# 1-Schematic_LoRaRice_node1.net
KiCad netlist of a schematic drawn in EasyEDA
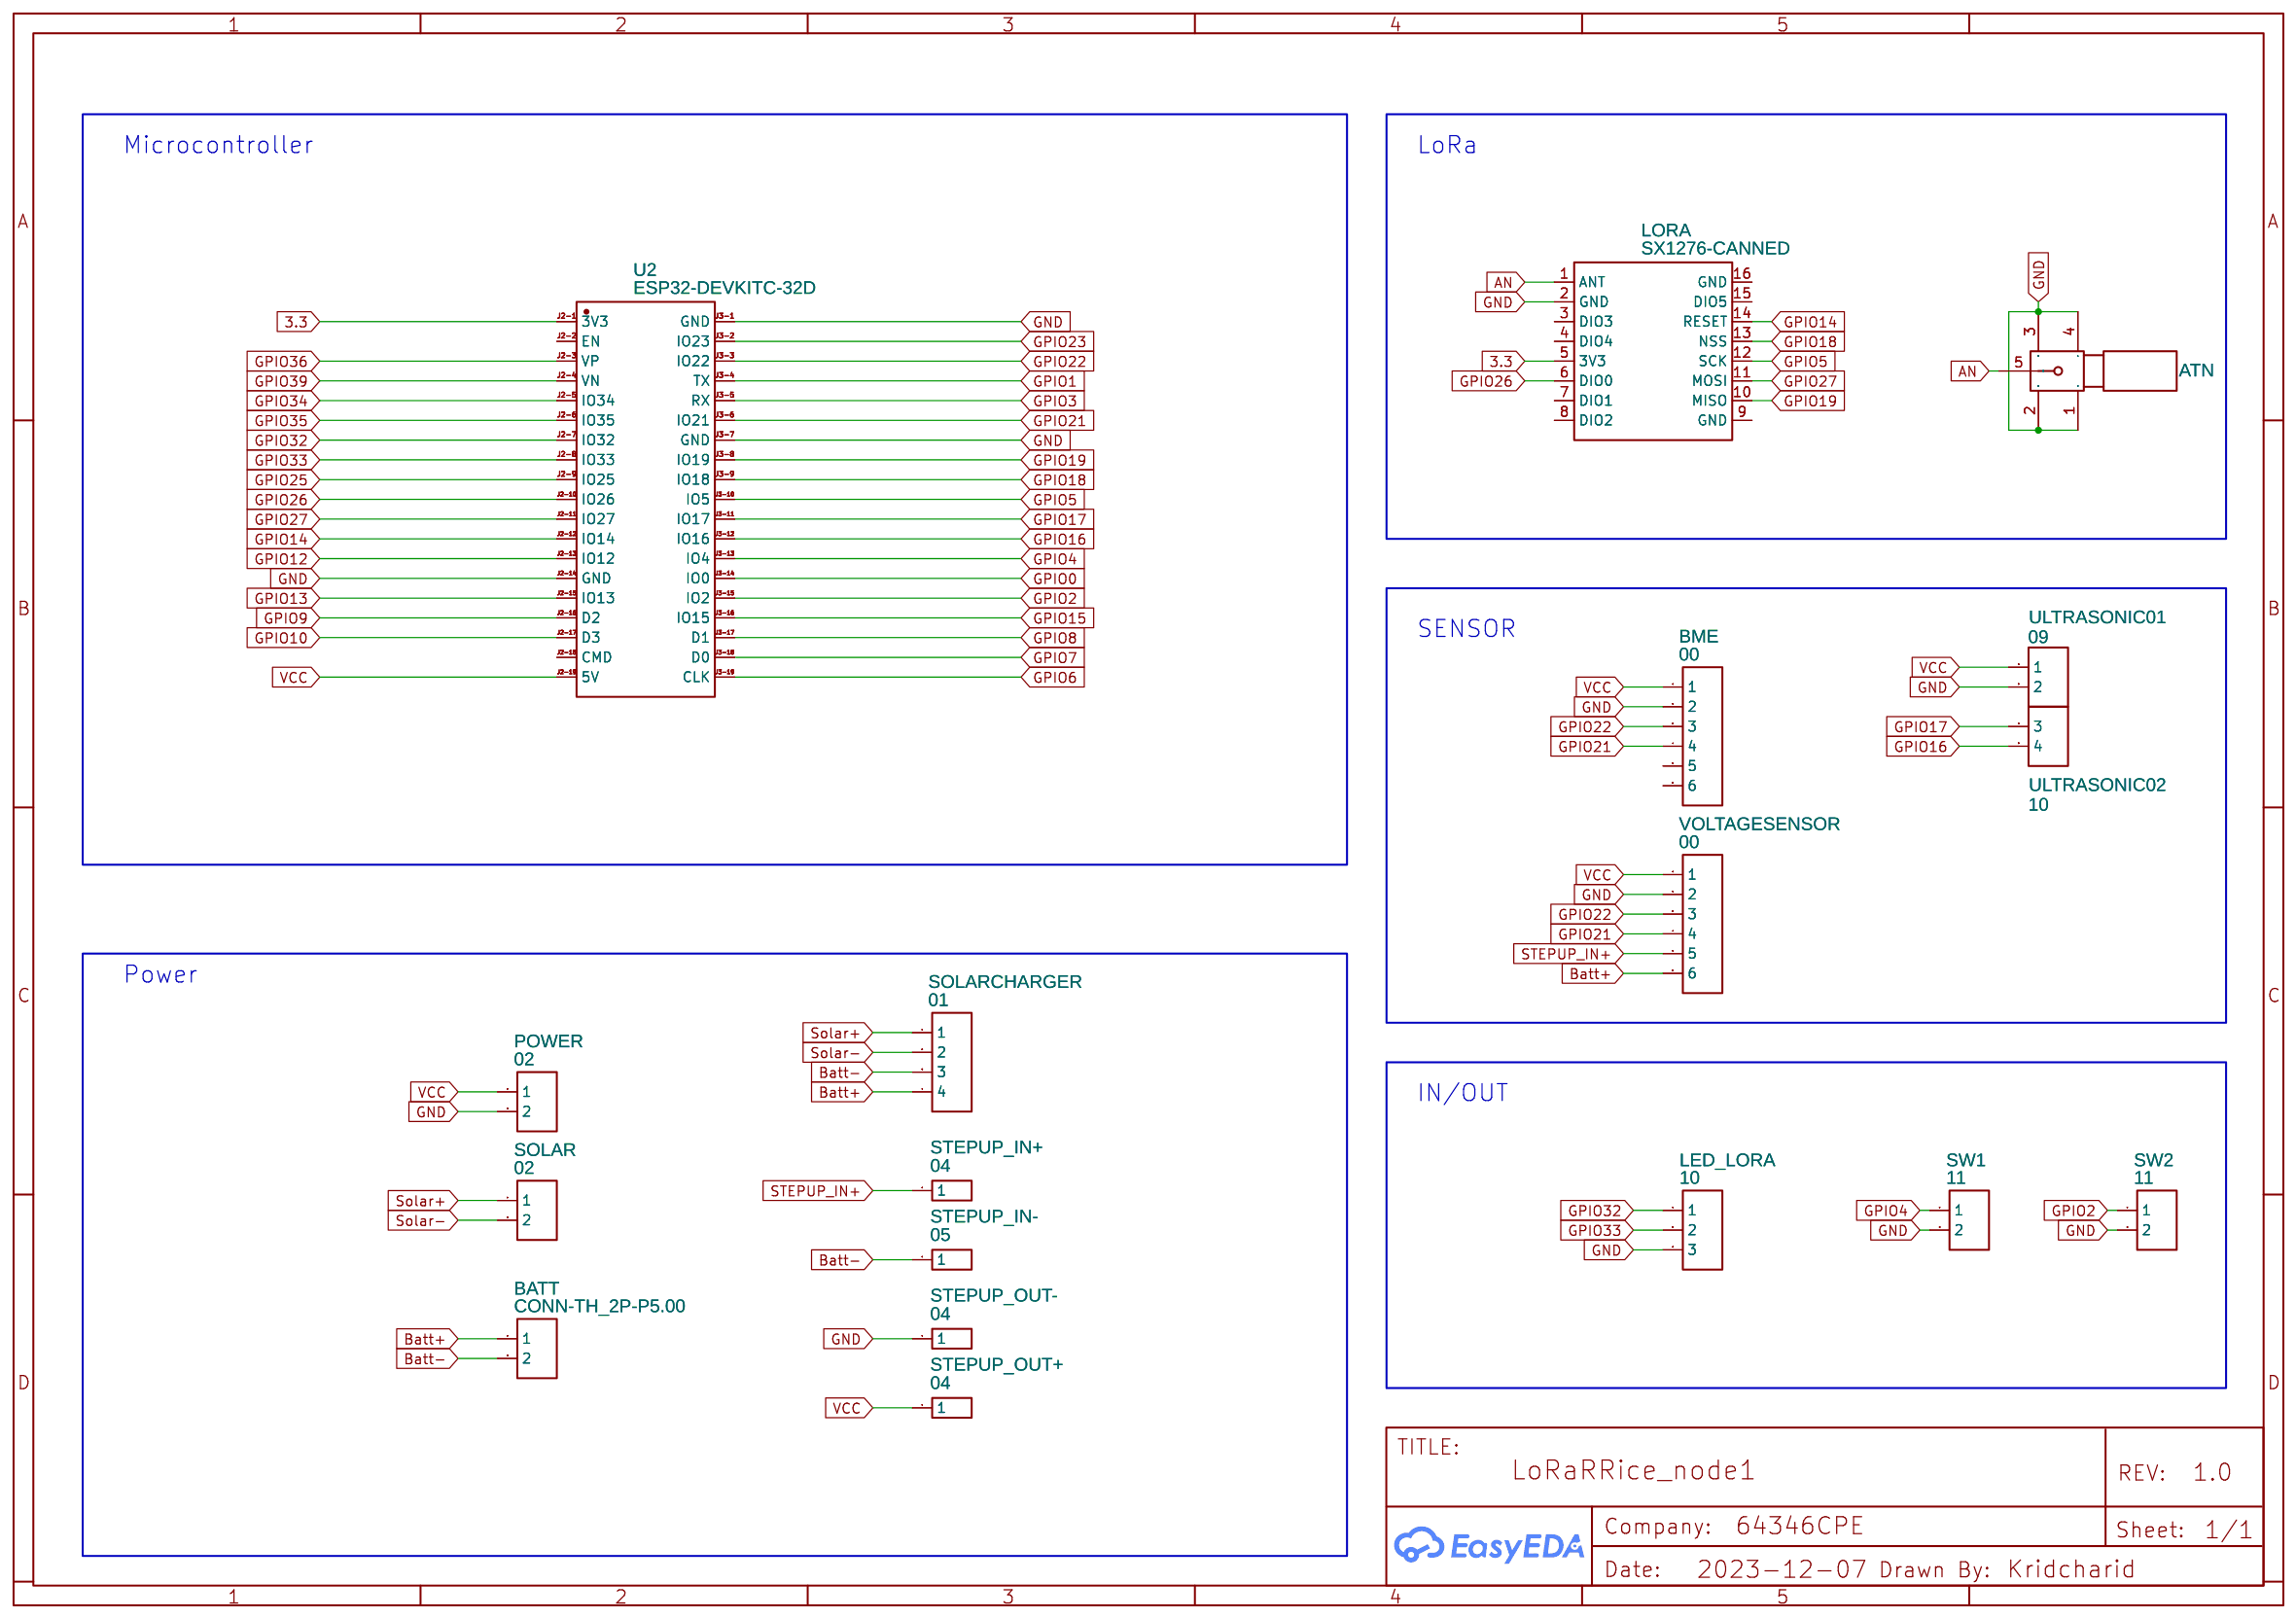
[diagram p0: schematic sheet]

(export (version "E")
  (design (tool "Eeschema 10.0.6"))
  (components
    (comp (ref "BATT") (value "CONN-TH_2P-P5.00") (libsource (lib "") (part "CONN-TH_2P-P5.00_5")))
    (comp (ref "BME") (value "00") (libsource (lib "") (part "HDR-F-2.54_1x6_1")))
    (comp (ref "LED_LORA") (value "10") (libsource (lib "") (part "CONN-TH_3P-P5.00")))
    (comp (ref "LORA")
      (value "SX1276-CANNED")
      (fields (field (name "Manufacturer Part") "LoRa1276-C1") (field (name "Manufacturer") "G-NiceRF"))
      (libsource (lib "") (part "SX1276-CANNED"))
    )
    (comp (ref "POWER") (value "02") (libsource (lib "") (part "CONN-TH_2P-P5.00")))
    (comp (ref "RF1")
      (value "ATN")
      (fields
        (field (name "Manufacturer Part") "BWSMA-KE-P001")
        (field (name "Manufacturer") "BAT WIRELESS(蝙蝠无线)")
      )
      (libsource (lib "") (part "BWSMA-KE-P001"))
    )
    (comp (ref "SOLAR") (value "02") (libsource (lib "") (part "CONN-TH_2P-P5.00_3")))
    (comp (ref "SOLARCHARGER") (value "01") (libsource (lib "") (part "HDR-F-2.54_1x4")))
    (comp (ref "STEPUP_IN+") (value "04") (libsource (lib "") (part "HDR-M-2.54_1x1")))
    (comp (ref "STEPUP_IN-") (value "05") (libsource (lib "") (part "HDR-M-2.54_1x1_3")))
    (comp (ref "STEPUP_OUT+") (value "04") (libsource (lib "") (part "HDR-M-2.54_1x1_2")))
    (comp (ref "STEPUP_OUT-") (value "04") (libsource (lib "") (part "HDR-M-2.54_1x1_1")))
    (comp (ref "SW1") (value "11") (libsource (lib "") (part "CONN-TH_2P-P5.00_2")))
    (comp (ref "SW2") (value "11") (libsource (lib "") (part "CONN-TH_2P-P5.00_2")))
    (comp (ref "U2")
      (value "ESP32-DEVKITC-32D")
      (fields
        (field (name "Manufacturer Part") "ESP32-DevKitC-32D")
        (field (name "Manufacturer") "ESPRESSIF(乐鑫)")
      )
      (libsource (lib "") (part "ESP32-DEVKITC-32D"))
    )
    (comp (ref "ULTRASONIC01") (value "09") (libsource (lib "") (part "CONN-TH_2P-P5.00_4")))
    (comp (ref "ULTRASONIC02") (value "10") (libsource (lib "") (part "CONN-TH_2P-P5.00_1")))
    (comp (ref "VOLTAGESENSOR") (value "00") (libsource (lib "") (part "HDR-F-2.54_1x6")))
  )
  (nets
    (net (code "1") (name "3.3") (class "Default")
      (node (ref "LORA") (pin "5") (pinfunction "3V3_5") (pintype "unspecified"))
      (node (ref "U2") (pin "J2-1") (pinfunction "3V3_J2-1") (pintype "unspecified"))
    )
    (net (code "2") (name "AN") (class "Default")
      (node (ref "LORA") (pin "1") (pinfunction "ANT_1") (pintype "unspecified"))
      (node (ref "RF1") (pin "5") (pinfunction "5_5") (pintype "unspecified"))
    )
    (net (code "3") (name "Batt+") (class "Default")
      (node (ref "BATT") (pin "1") (pinfunction "1_1") (pintype "unspecified"))
      (node (ref "SOLARCHARGER") (pin "4") (pinfunction "4_4") (pintype "unspecified"))
      (node (ref "VOLTAGESENSOR") (pin "6") (pinfunction "6_6") (pintype "input"))
    )
    (net (code "4") (name "Batt-") (class "Default")
      (node (ref "BATT") (pin "2") (pinfunction "2_2") (pintype "unspecified"))
      (node (ref "SOLARCHARGER") (pin "3") (pinfunction "3_3") (pintype "unspecified"))
      (node (ref "STEPUP_IN-") (pin "1") (pinfunction "1_1") (pintype "input"))
    )
    (net (code "5") (name "GND") (class "Default")
      (node (ref "BME") (pin "2") (pinfunction "2_2") (pintype "input"))
      (node (ref "LED_LORA") (pin "3") (pinfunction "3_3") (pintype "unspecified"))
      (node (ref "LORA") (pin "2") (pinfunction "GND_2") (pintype "unspecified"))
      (node (ref "POWER") (pin "2") (pinfunction "2_2") (pintype "unspecified"))
      (node (ref "RF1") (pin "1") (pinfunction "1_1") (pintype "unspecified"))
      (node (ref "RF1") (pin "2") (pinfunction "2_2") (pintype "unspecified"))
      (node (ref "RF1") (pin "3") (pinfunction "3_3") (pintype "unspecified"))
      (node (ref "RF1") (pin "4") (pinfunction "4_4") (pintype "unspecified"))
      (node (ref "STEPUP_OUT-") (pin "1") (pinfunction "1_1") (pintype "input"))
      (node (ref "SW1") (pin "2") (pinfunction "2_2") (pintype "unspecified"))
      (node (ref "SW2") (pin "2") (pinfunction "2_2") (pintype "unspecified"))
      (node (ref "U2") (pin "J2-14") (pinfunction "GND_J2-14") (pintype "unspecified"))
      (node (ref "U2") (pin "J3-1") (pinfunction "GND_J3-1") (pintype "unspecified"))
      (node (ref "U2") (pin "J3-7") (pinfunction "GND_J3-7") (pintype "unspecified"))
      (node (ref "ULTRASONIC01") (pin "2") (pinfunction "2_2") (pintype "unspecified"))
      (node (ref "VOLTAGESENSOR") (pin "2") (pinfunction "2_2") (pintype "input"))
    )
    (net (code "6") (name "GPIO0") (class "Default")
      (node (ref "U2") (pin "J3-14") (pinfunction "IO0_J3-14") (pintype "unspecified"))
    )
    (net (code "7") (name "GPIO1") (class "Default")
      (node (ref "U2") (pin "J3-4") (pinfunction "TX_J3-4") (pintype "unspecified"))
    )
    (net (code "8") (name "GPIO2") (class "Default")
      (node (ref "SW2") (pin "1") (pinfunction "1_1") (pintype "unspecified"))
      (node (ref "U2") (pin "J3-15") (pinfunction "IO2_J3-15") (pintype "unspecified"))
    )
    (net (code "9") (name "GPIO3") (class "Default")
      (node (ref "U2") (pin "J3-5") (pinfunction "RX_J3-5") (pintype "unspecified"))
    )
    (net (code "10") (name "GPIO4") (class "Default")
      (node (ref "SW1") (pin "1") (pinfunction "1_1") (pintype "unspecified"))
      (node (ref "U2") (pin "J3-13") (pinfunction "IO4_J3-13") (pintype "unspecified"))
    )
    (net (code "11") (name "GPIO5") (class "Default")
      (node (ref "LORA") (pin "12") (pinfunction "SCK_12") (pintype "unspecified"))
      (node (ref "U2") (pin "J3-10") (pinfunction "IO5_J3-10") (pintype "unspecified"))
    )
    (net (code "12") (name "GPIO6") (class "Default")
      (node (ref "U2") (pin "J3-19") (pinfunction "CLK_J3-19") (pintype "unspecified"))
    )
    (net (code "13") (name "GPIO7") (class "Default")
      (node (ref "U2") (pin "J3-18") (pinfunction "D0_J3-18") (pintype "unspecified"))
    )
    (net (code "14") (name "GPIO8") (class "Default")
      (node (ref "U2") (pin "J3-17") (pinfunction "D1_J3-17") (pintype "unspecified"))
    )
    (net (code "15") (name "GPIO9") (class "Default")
      (node (ref "U2") (pin "J2-16") (pinfunction "D2_J2-16") (pintype "unspecified"))
    )
    (net (code "16") (name "GPIO10") (class "Default")
      (node (ref "U2") (pin "J2-17") (pinfunction "D3_J2-17") (pintype "unspecified"))
    )
    (net (code "17") (name "GPIO12") (class "Default")
      (node (ref "U2") (pin "J2-13") (pinfunction "IO12_J2-13") (pintype "unspecified"))
    )
    (net (code "18") (name "GPIO13") (class "Default")
      (node (ref "U2") (pin "J2-15") (pinfunction "IO13_J2-15") (pintype "unspecified"))
    )
    (net (code "19") (name "GPIO14") (class "Default")
      (node (ref "LORA") (pin "14") (pinfunction "RESET_14") (pintype "unspecified"))
      (node (ref "U2") (pin "J2-12") (pinfunction "IO14_J2-12") (pintype "unspecified"))
    )
    (net (code "20") (name "GPIO15") (class "Default")
      (node (ref "U2") (pin "J3-16") (pinfunction "IO15_J3-16") (pintype "unspecified"))
    )
    (net (code "21") (name "GPIO16") (class "Default")
      (node (ref "U2") (pin "J3-12") (pinfunction "IO16_J3-12") (pintype "unspecified"))
      (node (ref "ULTRASONIC02") (pin "2") (pinfunction "4_2") (pintype "unspecified"))
    )
    (net (code "22") (name "GPIO17") (class "Default")
      (node (ref "U2") (pin "J3-11") (pinfunction "IO17_J3-11") (pintype "unspecified"))
      (node (ref "ULTRASONIC02") (pin "1") (pinfunction "3_1") (pintype "unspecified"))
    )
    (net (code "23") (name "GPIO18") (class "Default")
      (node (ref "LORA") (pin "13") (pinfunction "NSS_13") (pintype "unspecified"))
      (node (ref "U2") (pin "J3-9") (pinfunction "IO18_J3-9") (pintype "unspecified"))
    )
    (net (code "24") (name "GPIO19") (class "Default")
      (node (ref "LORA") (pin "10") (pinfunction "MISO_10") (pintype "unspecified"))
      (node (ref "U2") (pin "J3-8") (pinfunction "IO19_J3-8") (pintype "unspecified"))
    )
    (net (code "25") (name "GPIO21") (class "Default")
      (node (ref "BME") (pin "4") (pinfunction "4_4") (pintype "input"))
      (node (ref "U2") (pin "J3-6") (pinfunction "IO21_J3-6") (pintype "unspecified"))
      (node (ref "VOLTAGESENSOR") (pin "4") (pinfunction "4_4") (pintype "input"))
    )
    (net (code "26") (name "GPIO22") (class "Default")
      (node (ref "BME") (pin "3") (pinfunction "3_3") (pintype "input"))
      (node (ref "U2") (pin "J3-3") (pinfunction "IO22_J3-3") (pintype "unspecified"))
      (node (ref "VOLTAGESENSOR") (pin "3") (pinfunction "3_3") (pintype "input"))
    )
    (net (code "27") (name "GPIO23") (class "Default")
      (node (ref "U2") (pin "J3-2") (pinfunction "IO23_J3-2") (pintype "unspecified"))
    )
    (net (code "28") (name "GPIO25") (class "Default")
      (node (ref "U2") (pin "J2-9") (pinfunction "IO25_J2-9") (pintype "unspecified"))
    )
    (net (code "29") (name "GPIO26") (class "Default")
      (node (ref "LORA") (pin "6") (pinfunction "DIO0_6") (pintype "unspecified"))
      (node (ref "U2") (pin "J2-10") (pinfunction "IO26_J2-10") (pintype "unspecified"))
    )
    (net (code "30") (name "GPIO27") (class "Default")
      (node (ref "LORA") (pin "11") (pinfunction "MOSI_11") (pintype "unspecified"))
      (node (ref "U2") (pin "J2-11") (pinfunction "IO27_J2-11") (pintype "unspecified"))
    )
    (net (code "31") (name "GPIO32") (class "Default")
      (node (ref "LED_LORA") (pin "1") (pinfunction "1_1") (pintype "unspecified"))
      (node (ref "U2") (pin "J2-7") (pinfunction "IO32_J2-7") (pintype "unspecified"))
    )
    (net (code "32") (name "GPIO33") (class "Default")
      (node (ref "LED_LORA") (pin "2") (pinfunction "2_2") (pintype "unspecified"))
      (node (ref "U2") (pin "J2-8") (pinfunction "IO33_J2-8") (pintype "unspecified"))
    )
    (net (code "33") (name "GPIO34") (class "Default")
      (node (ref "U2") (pin "J2-5") (pinfunction "IO34_J2-5") (pintype "unspecified"))
    )
    (net (code "34") (name "GPIO35") (class "Default")
      (node (ref "U2") (pin "J2-6") (pinfunction "IO35_J2-6") (pintype "unspecified"))
    )
    (net (code "35") (name "GPIO36") (class "Default")
      (node (ref "U2") (pin "J2-3") (pinfunction "VP_J2-3") (pintype "unspecified"))
    )
    (net (code "36") (name "GPIO39") (class "Default")
      (node (ref "U2") (pin "J2-4") (pinfunction "VN_J2-4") (pintype "unspecified"))
    )
    (net (code "37") (name "STEPUP_IN+") (class "Default")
      (node (ref "STEPUP_IN+") (pin "1") (pinfunction "1_1") (pintype "input"))
      (node (ref "VOLTAGESENSOR") (pin "5") (pinfunction "5_5") (pintype "input"))
    )
    (net (code "38") (name "Solar+") (class "Default")
      (node (ref "SOLAR") (pin "1") (pinfunction "1_1") (pintype "unspecified"))
      (node (ref "SOLARCHARGER") (pin "1") (pinfunction "1_1") (pintype "unspecified"))
    )
    (net (code "39") (name "Solar-") (class "Default")
      (node (ref "SOLAR") (pin "2") (pinfunction "2_2") (pintype "unspecified"))
      (node (ref "SOLARCHARGER") (pin "2") (pinfunction "2_2") (pintype "unspecified"))
    )
    (net (code "40") (name "VCC") (class "Default")
      (node (ref "BME") (pin "1") (pinfunction "1_1") (pintype "input"))
      (node (ref "POWER") (pin "1") (pinfunction "1_1") (pintype "unspecified"))
      (node (ref "STEPUP_OUT+") (pin "1") (pinfunction "1_1") (pintype "input"))
      (node (ref "U2") (pin "J2-19") (pinfunction "5V_J2-19") (pintype "unspecified"))
      (node (ref "ULTRASONIC01") (pin "1") (pinfunction "1_1") (pintype "unspecified"))
      (node (ref "VOLTAGESENSOR") (pin "1") (pinfunction "1_1") (pintype "input"))
    )
    (net (code "41") (name "unconnected-(BME-Pad5)") (class "Default")
      (node (ref "BME") (pin "5") (pinfunction "5_5") (pintype "input"))
    )
    (net (code "42") (name "unconnected-(BME-Pad6)") (class "Default")
      (node (ref "BME") (pin "6") (pinfunction "6_6") (pintype "input"))
    )
    (net (code "43") (name "unconnected-(LORA-DIO1-Pad7)") (class "Default")
      (node (ref "LORA") (pin "7") (pinfunction "DIO1_7") (pintype "unspecified"))
    )
    (net (code "44") (name "unconnected-(LORA-DIO2-Pad8)") (class "Default")
      (node (ref "LORA") (pin "8") (pinfunction "DIO2_8") (pintype "unspecified"))
    )
    (net (code "45") (name "unconnected-(LORA-DIO3-Pad3)") (class "Default")
      (node (ref "LORA") (pin "3") (pinfunction "DIO3_3") (pintype "unspecified"))
    )
    (net (code "46") (name "unconnected-(LORA-DIO4-Pad4)") (class "Default")
      (node (ref "LORA") (pin "4") (pinfunction "DIO4_4") (pintype "unspecified"))
    )
    (net (code "47") (name "unconnected-(LORA-DIO5-Pad15)") (class "Default")
      (node (ref "LORA") (pin "15") (pinfunction "DIO5_15") (pintype "unspecified"))
    )
    (net (code "48") (name "unconnected-(LORA-GND-Pad9)") (class "Default")
      (node (ref "LORA") (pin "9") (pinfunction "GND_9") (pintype "unspecified"))
    )
    (net (code "49") (name "unconnected-(LORA-GND-Pad16)") (class "Default")
      (node (ref "LORA") (pin "16") (pinfunction "GND_16") (pintype "unspecified"))
    )
    (net (code "50") (name "unconnected-(U2-CMD-PadJ2-18)") (class "Default")
      (node (ref "U2") (pin "J2-18") (pinfunction "CMD_J2-18") (pintype "unspecified"))
    )
    (net (code "51") (name "unconnected-(U2-EN-PadJ2-2)") (class "Default")
      (node (ref "U2") (pin "J2-2") (pinfunction "EN_J2-2") (pintype "unspecified"))
    )
  )
)
